# Extend.net
KiCad netlist of a schematic drawn in Altium Designer
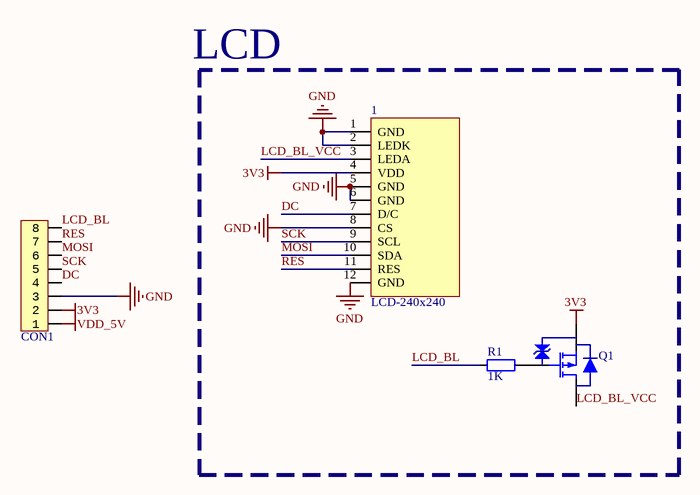
[diagram p0: Extend.SchDoc]

(export (version "E")
  (design (tool "Eeschema 10.0.6"))
  (components
    (comp (ref "1")
      (value "LCD-240x240")
      (footprint "LCD-240x240-NoHole")
      (description "显示屏")
      (libsource (lib "mLib") (part "LCD-240x240"))
    )
    (comp (ref "CON1")
      (value "FFC_0.5_8")
      (footprint "FFC_0.5_8")
      (description "FFC")
      (libsource (lib "KitSprout") (part "FFC_0.5_8"))
    )
    (comp (ref "Q1")
      (value "AO3415A")
      (footprint "SOT23-3")
      (description "MOSFET")
      (fields (field (name "PUBLISHER") "Altium Limited"))
      (libsource (lib "MyPcbLib") (part "AO3415A"))
    )
    (comp (ref "R1")
      (value "1K")
      (footprint "RES_0402")
      (description "Resistor")
      (libsource (lib "MyPcbLib") (part "电阻-0402"))
    )
  )
  (nets
    (net (code "1") (name "/DC") (class "Default")
      (node (ref "1") (pin "7") (pinfunction "D/C_7") (pintype "passive"))
      (node (ref "CON1") (pin "4") (pinfunction "4_4") (pintype "passive"))
    )
    (net (code "2") (name "/LCD_BL") (class "Default")
      (node (ref "CON1") (pin "8") (pinfunction "8_8") (pintype "passive"))
      (node (ref "R1") (pin "1") (pinfunction "1_1") (pintype "passive"))
    )
    (net (code "3") (name "/LCD_BL_VCC") (class "Default")
      (node (ref "1") (pin "3") (pinfunction "LEDA_3") (pintype "passive"))
      (node (ref "Q1") (pin "3") (pinfunction "D_3") (pintype "passive"))
    )
    (net (code "4") (name "/MOSI") (class "Default")
      (node (ref "1") (pin "10") (pinfunction "SDA_10") (pintype "passive"))
      (node (ref "CON1") (pin "6") (pinfunction "6_6") (pintype "passive"))
    )
    (net (code "5") (name "/RES") (class "Default")
      (node (ref "1") (pin "11") (pinfunction "RES_11") (pintype "passive"))
      (node (ref "CON1") (pin "7") (pinfunction "7_7") (pintype "passive"))
    )
    (net (code "6") (name "/SCK") (class "Default")
      (node (ref "1") (pin "9") (pinfunction "SCL_9") (pintype "passive"))
      (node (ref "CON1") (pin "5") (pinfunction "5_5") (pintype "passive"))
    )
    (net (code "7") (name "3V3") (class "Default")
      (node (ref "1") (pin "4") (pinfunction "VDD_4") (pintype "passive"))
      (node (ref "CON1") (pin "2") (pinfunction "2_2") (pintype "passive"))
      (node (ref "Q1") (pin "2") (pinfunction "S_2") (pintype "passive"))
    )
    (net (code "8") (name "GND") (class "Default")
      (node (ref "1") (pin "1") (pinfunction "GND_1") (pintype "passive"))
      (node (ref "1") (pin "12") (pinfunction "GND_12") (pintype "passive"))
      (node (ref "1") (pin "2") (pinfunction "LEDK_2") (pintype "passive"))
      (node (ref "1") (pin "5") (pinfunction "GND_5") (pintype "passive"))
      (node (ref "1") (pin "6") (pinfunction "GND_6") (pintype "passive"))
      (node (ref "1") (pin "8") (pinfunction "CS_8") (pintype "passive"))
      (node (ref "CON1") (pin "3") (pinfunction "3_3") (pintype "passive"))
    )
    (net (code "9") (name "Net-(Q1-G)") (class "Default")
      (node (ref "Q1") (pin "1") (pinfunction "G_1") (pintype "passive"))
      (node (ref "R1") (pin "2") (pinfunction "2_2") (pintype "passive"))
    )
    (net (code "10") (name "VDD_5V") (class "Default")
      (node (ref "CON1") (pin "1") (pinfunction "1_1") (pintype "passive"))
    )
  )
)
